# OSSIBeacon.net
KiCad netlist of a schematic drawn in EAGLE
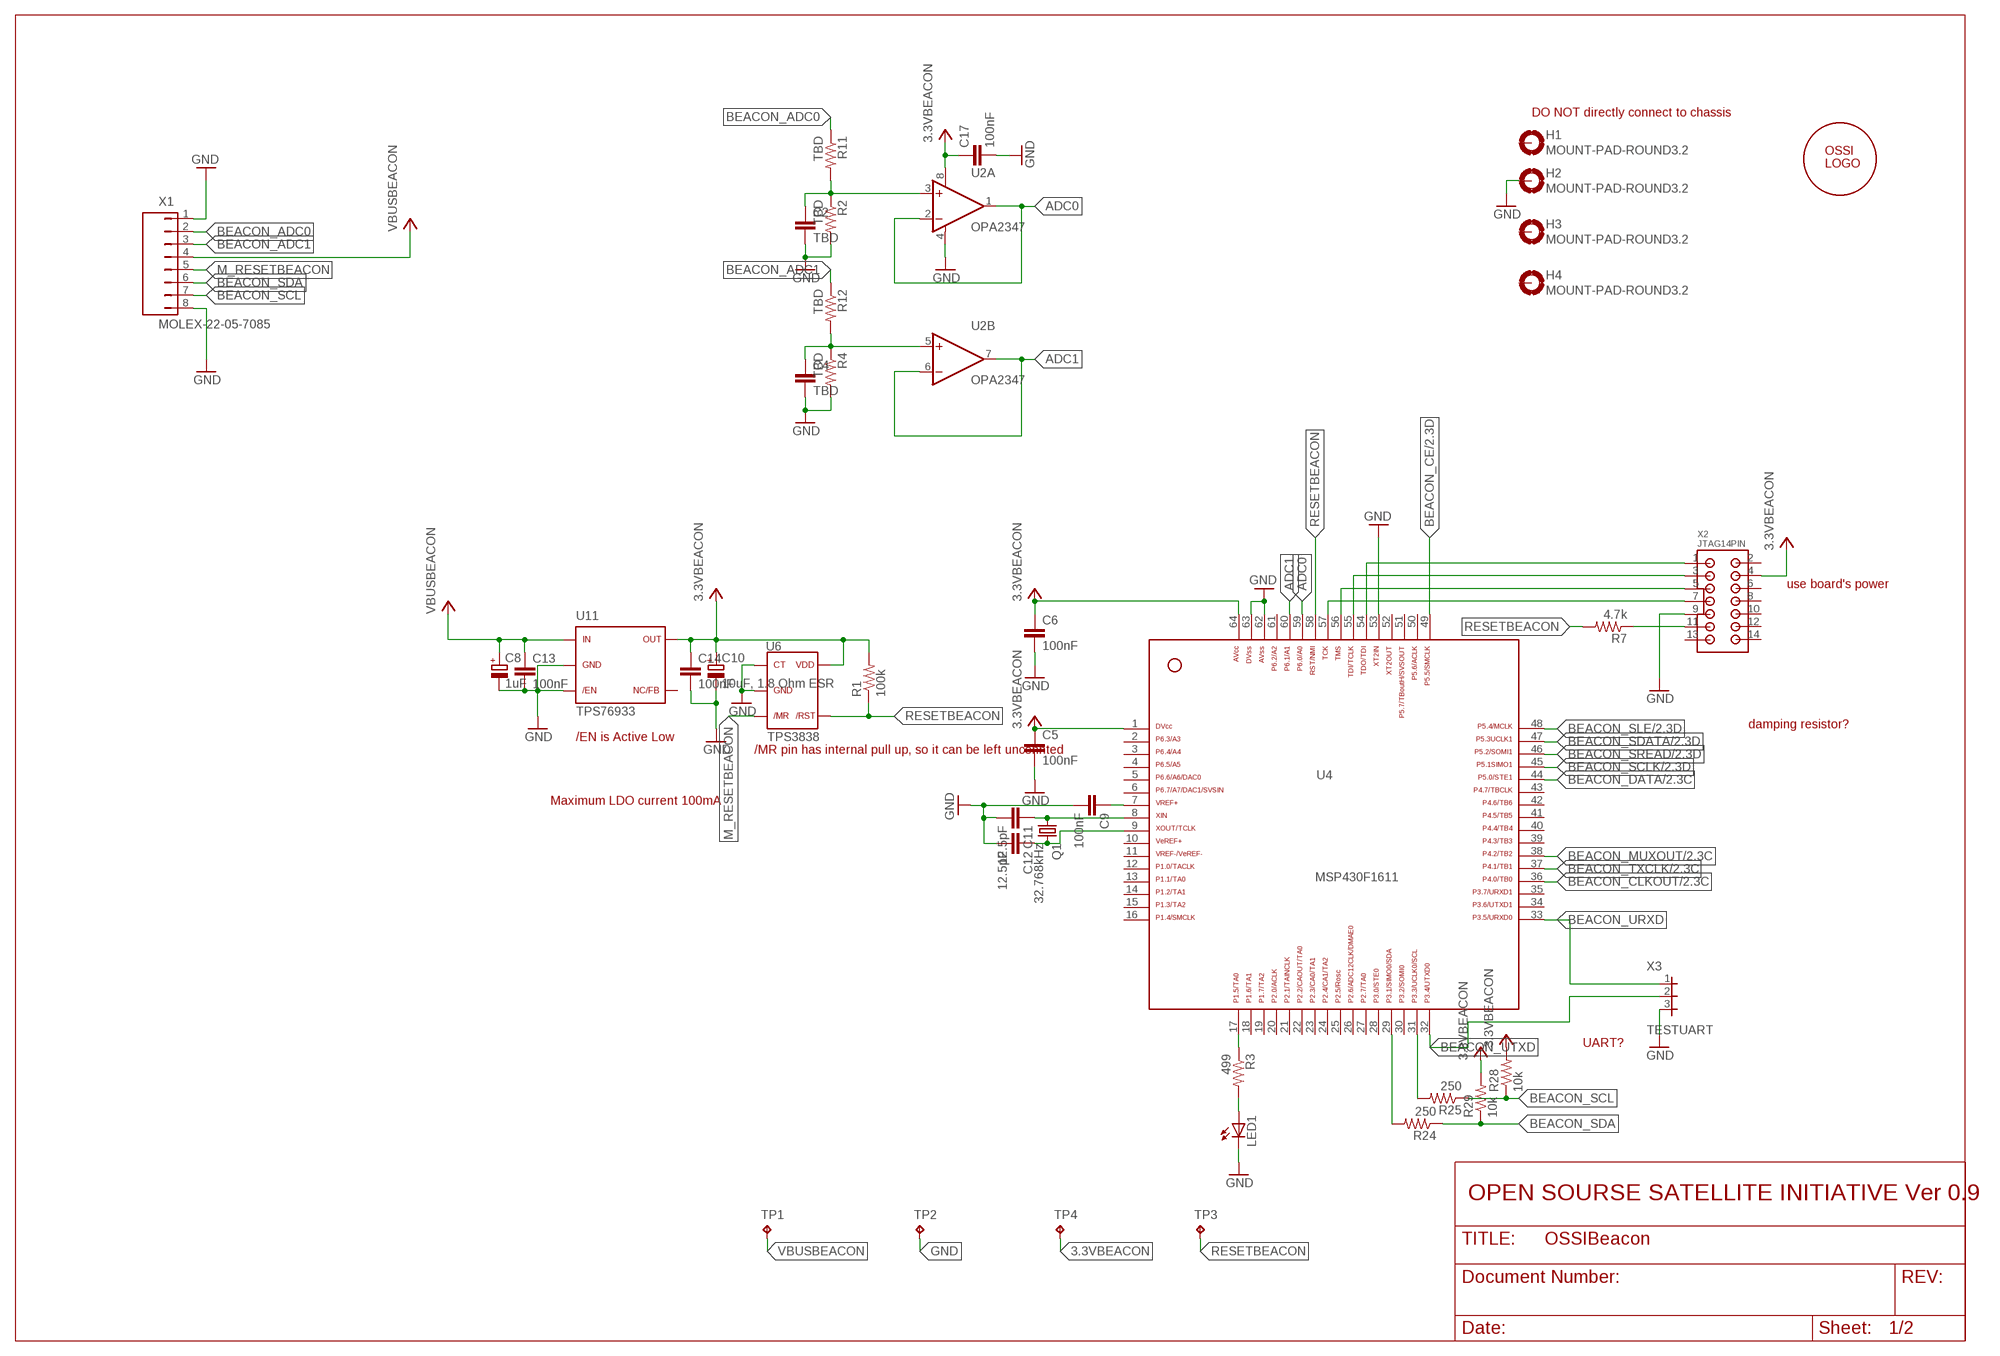
[diagram p0: schematic, sheet 1]
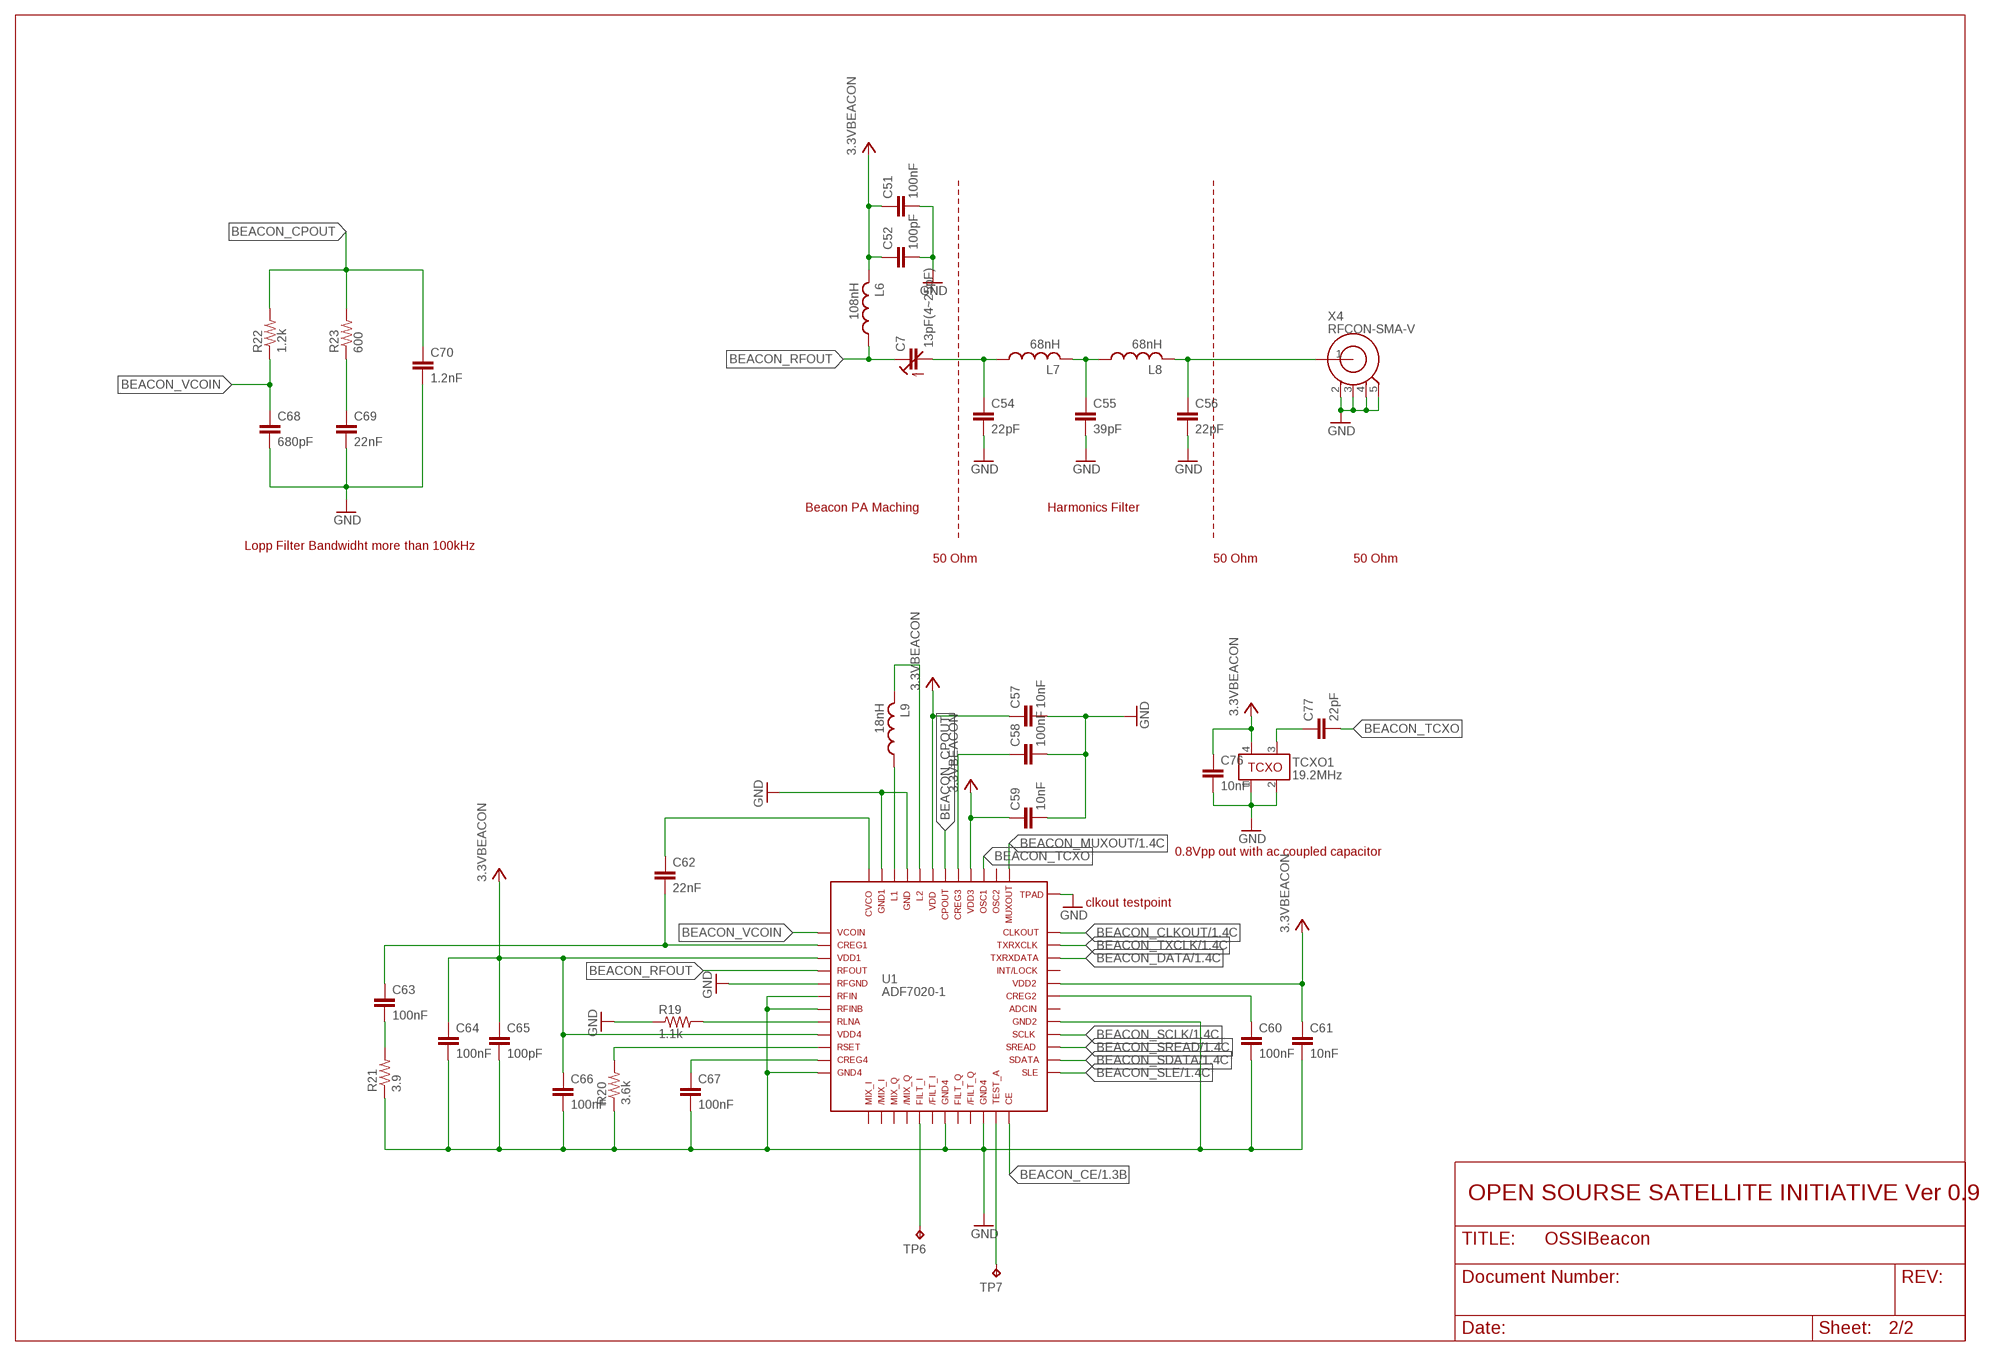
[diagram p1: schematic, sheet 2]

(export (version "E")
  (design (tool "Eeschema 10.0.6"))
  (components
    (comp (ref "C7")
      (value "13pF(4~25pF)")
      (footprint "eagle-import:TZB4Z250BA10R00")
      (libsource (lib "eagle-import") (part "C-TRIMM"))
    )
    (comp (ref "C51")
      (value "100nF")
      (footprint "eagle-import:C0603(1608)")
      (libsource (lib "eagle-import") (part "C0603(1608)"))
    )
    (comp (ref "C52")
      (value "100pF")
      (footprint "eagle-import:C0603(1608)")
      (libsource (lib "eagle-import") (part "C0603(1608)"))
    )
    (comp (ref "C54")
      (value "22pF")
      (footprint "eagle-import:C0603(1608)")
      (libsource (lib "eagle-import") (part "C0603(1608)"))
    )
    (comp (ref "C55")
      (value "39pF")
      (footprint "eagle-import:C0603(1608)")
      (libsource (lib "eagle-import") (part "C0603(1608)"))
    )
    (comp (ref "C56")
      (value "22pF")
      (footprint "eagle-import:C0603(1608)")
      (libsource (lib "eagle-import") (part "C0603(1608)"))
    )
    (comp (ref "C57")
      (value "10nF")
      (footprint "eagle-import:C0603(1608)")
      (libsource (lib "eagle-import") (part "C0603(1608)"))
    )
    (comp (ref "C58")
      (value "100nF")
      (footprint "eagle-import:C0603(1608)")
      (libsource (lib "eagle-import") (part "C0603(1608)"))
    )
    (comp (ref "C59")
      (value "10nF")
      (footprint "eagle-import:C0603(1608)")
      (libsource (lib "eagle-import") (part "C0603(1608)"))
    )
    (comp (ref "C60")
      (value "100nF")
      (footprint "eagle-import:C0603(1608)")
      (libsource (lib "eagle-import") (part "C0603(1608)"))
    )
    (comp (ref "C61")
      (value "10nF")
      (footprint "eagle-import:C0603(1608)")
      (libsource (lib "eagle-import") (part "C0603(1608)"))
    )
    (comp (ref "C62")
      (value "22nF")
      (footprint "eagle-import:C0603(1608)")
      (libsource (lib "eagle-import") (part "C0603(1608)"))
    )
    (comp (ref "C63")
      (value "100nF")
      (footprint "eagle-import:C0603(1608)")
      (libsource (lib "eagle-import") (part "C0603(1608)"))
    )
    (comp (ref "C64")
      (value "100nF")
      (footprint "eagle-import:C0603(1608)")
      (libsource (lib "eagle-import") (part "C0603(1608)"))
    )
    (comp (ref "C65")
      (value "100pF")
      (footprint "eagle-import:C0603(1608)")
      (libsource (lib "eagle-import") (part "C0603(1608)"))
    )
    (comp (ref "C66")
      (value "100nF")
      (footprint "eagle-import:C0603(1608)")
      (libsource (lib "eagle-import") (part "C0603(1608)"))
    )
    (comp (ref "C67")
      (value "100nF")
      (footprint "eagle-import:C0603(1608)")
      (libsource (lib "eagle-import") (part "C0603(1608)"))
    )
    (comp (ref "C68")
      (value "680pF")
      (footprint "eagle-import:C0603(1608)")
      (libsource (lib "eagle-import") (part "C0603(1608)"))
    )
    (comp (ref "C69")
      (value "22nF")
      (footprint "eagle-import:C0603(1608)")
      (libsource (lib "eagle-import") (part "C0603(1608)"))
    )
    (comp (ref "C70")
      (value "1.2nF")
      (footprint "eagle-import:C0603(1608)")
      (libsource (lib "eagle-import") (part "C0603(1608)"))
    )
    (comp (ref "C76")
      (value "10nF")
      (footprint "eagle-import:C0603(1608)")
      (libsource (lib "eagle-import") (part "C0603(1608)"))
    )
    (comp (ref "C77")
      (value "22pF")
      (footprint "eagle-import:C0603(1608)")
      (libsource (lib "eagle-import") (part "C0603(1608)"))
    )
    (comp (ref "L6")
      (value "108nH")
      (footprint "eagle-import:L0603(1608)")
      (libsource (lib "eagle-import") (part "L0603(1608)"))
    )
    (comp (ref "L7")
      (value "68nH")
      (footprint "eagle-import:L0603(1608)")
      (libsource (lib "eagle-import") (part "L0603(1608)"))
    )
    (comp (ref "L8")
      (value "68nH")
      (footprint "eagle-import:L0603(1608)")
      (libsource (lib "eagle-import") (part "L0603(1608)"))
    )
    (comp (ref "L9")
      (value "18nH")
      (footprint "eagle-import:L0603(1608)")
      (libsource (lib "eagle-import") (part "L0603(1608)"))
    )
    (comp (ref "R19")
      (value "1.1k")
      (footprint "eagle-import:R0603(1608)")
      (libsource (lib "eagle-import") (part "R0603(1608)"))
    )
    (comp (ref "R20")
      (value "3.6k")
      (footprint "eagle-import:R0603(1608)")
      (libsource (lib "eagle-import") (part "R0603(1608)"))
    )
    (comp (ref "R21")
      (value "3.9")
      (footprint "eagle-import:R0603(1608)")
      (libsource (lib "eagle-import") (part "R0603(1608)"))
    )
    (comp (ref "R22")
      (value "1.2k")
      (footprint "eagle-import:R0603(1608)")
      (libsource (lib "eagle-import") (part "R0603(1608)"))
    )
    (comp (ref "R23")
      (value "600")
      (footprint "eagle-import:R0603(1608)")
      (libsource (lib "eagle-import") (part "R0603(1608)"))
    )
    (comp (ref "TCXO1")
      (value "19.2MHz")
      (footprint "eagle-import:TCXO_M532")
      (libsource (lib "eagle-import") (part "TCXO-M532"))
    )
    (comp (ref "TP6")
      (value "TP")
      (footprint "eagle-import:TP-13")
      (libsource (lib "eagle-import") (part "TP"))
    )
    (comp (ref "TP7")
      (value "TP")
      (footprint "eagle-import:TP-13")
      (libsource (lib "eagle-import") (part "TP"))
    )
    (comp (ref "U1")
      (value "ADF7020-1")
      (footprint "eagle-import:LFCSP48")
      (libsource (lib "eagle-import") (part "ADF7020-1"))
    )
    (comp (ref "X4")
      (value "RFCON-SMA-V")
      (footprint "eagle-import:SMA-V")
      (libsource (lib "eagle-import") (part "RFCON-SMA-V"))
    )
    (comp (ref "C2")
      (value "TBD")
      (footprint "eagle-import:C0603(1608)")
      (libsource (lib "eagle-import") (part "C0603(1608)"))
    )
    (comp (ref "C4")
      (value "TBD")
      (footprint "eagle-import:C0603(1608)")
      (libsource (lib "eagle-import") (part "C0603(1608)"))
    )
    (comp (ref "C5")
      (value "100nF")
      (footprint "eagle-import:C0603(1608)")
      (libsource (lib "eagle-import") (part "C0603(1608)"))
    )
    (comp (ref "C6")
      (value "100nF")
      (footprint "eagle-import:C0603(1608)")
      (libsource (lib "eagle-import") (part "C0603(1608)"))
    )
    (comp (ref "C8")
      (value "1uF")
      (footprint "eagle-import:C1206(3216)-A")
      (libsource (lib "eagle-import") (part "C-TANTAL-A"))
    )
    (comp (ref "C9")
      (value "100nF")
      (footprint "eagle-import:C0603(1608)")
      (libsource (lib "eagle-import") (part "C0603(1608)"))
    )
    (comp (ref "C10")
      (value "10uF, 1.8 Ohm ESR")
      (footprint "eagle-import:C2312(6032)-C")
      (libsource (lib "eagle-import") (part "C-TANTAL-C"))
    )
    (comp (ref "C11")
      (value "12.5pF")
      (footprint "eagle-import:C0603(1608)")
      (libsource (lib "eagle-import") (part "C0603(1608)"))
    )
    (comp (ref "C12")
      (value "12.5pF")
      (footprint "eagle-import:C0603(1608)")
      (libsource (lib "eagle-import") (part "C0603(1608)"))
    )
    (comp (ref "C13")
      (value "100nF")
      (footprint "eagle-import:C0603(1608)")
      (libsource (lib "eagle-import") (part "C0603(1608)"))
    )
    (comp (ref "C14")
      (value "100nF")
      (footprint "eagle-import:C0603(1608)")
      (libsource (lib "eagle-import") (part "C0603(1608)"))
    )
    (comp (ref "C17")
      (value "100nF")
      (footprint "eagle-import:C0603(1608)")
      (libsource (lib "eagle-import") (part "C0603(1608)"))
    )
    (comp (ref "H1")
      (value "MOUNT-PAD-ROUND3.2")
      (footprint "eagle-import:3.2-PAD-ROUND")
      (libsource (lib "eagle-import") (part "MOUNT-PAD-ROUND3.2"))
    )
    (comp (ref "H2")
      (value "MOUNT-PAD-ROUND3.2")
      (footprint "eagle-import:3.2-PAD-ROUND")
      (libsource (lib "eagle-import") (part "MOUNT-PAD-ROUND3.2"))
    )
    (comp (ref "H3")
      (value "MOUNT-PAD-ROUND3.2")
      (footprint "eagle-import:3.2-PAD-ROUND")
      (libsource (lib "eagle-import") (part "MOUNT-PAD-ROUND3.2"))
    )
    (comp (ref "H4")
      (value "MOUNT-PAD-ROUND3.2")
      (footprint "eagle-import:3.2-PAD-ROUND")
      (libsource (lib "eagle-import") (part "MOUNT-PAD-ROUND3.2"))
    )
    (comp (ref "LED1")
      (value "LED3MM")
      (footprint "eagle-import:LED3MM")
      (libsource (lib "eagle-import") (part "LED3MM"))
    )
    (comp (ref "Q1")
      (value "32.768kHz")
      (footprint "eagle-import:NX-3215")
      (libsource (lib "eagle-import") (part "NX-3215"))
    )
    (comp (ref "R1")
      (value "100k")
      (footprint "eagle-import:R0603(1608)")
      (libsource (lib "eagle-import") (part "R0603(1608)"))
    )
    (comp (ref "R2")
      (value "TBD")
      (footprint "eagle-import:R0603(1608)")
      (libsource (lib "eagle-import") (part "R0603(1608)"))
    )
    (comp (ref "R3")
      (value "499")
      (footprint "eagle-import:R0603(1608)")
      (libsource (lib "eagle-import") (part "R0603(1608)"))
    )
    (comp (ref "R4")
      (value "TBD")
      (footprint "eagle-import:R0603(1608)")
      (libsource (lib "eagle-import") (part "R0603(1608)"))
    )
    (comp (ref "R7")
      (value "4.7k")
      (footprint "eagle-import:R0603(1608)")
      (libsource (lib "eagle-import") (part "R0603(1608)"))
    )
    (comp (ref "R11")
      (value "TBD")
      (footprint "eagle-import:R0603(1608)")
      (libsource (lib "eagle-import") (part "R0603(1608)"))
    )
    (comp (ref "R12")
      (value "TBD")
      (footprint "eagle-import:R0603(1608)")
      (libsource (lib "eagle-import") (part "R0603(1608)"))
    )
    (comp (ref "R24")
      (value "250")
      (footprint "eagle-import:R0603(1608)")
      (libsource (lib "eagle-import") (part "R0603(1608)"))
    )
    (comp (ref "R25")
      (value "250")
      (footprint "eagle-import:R0603(1608)")
      (libsource (lib "eagle-import") (part "R0603(1608)"))
    )
    (comp (ref "R28")
      (value "10k")
      (footprint "eagle-import:R0603(1608)")
      (libsource (lib "eagle-import") (part "R0603(1608)"))
    )
    (comp (ref "R29")
      (value "10k")
      (footprint "eagle-import:R0603(1608)")
      (libsource (lib "eagle-import") (part "R0603(1608)"))
    )
    (comp (ref "TP1")
      (value "TP")
      (footprint "eagle-import:TP-13")
      (libsource (lib "eagle-import") (part "TP"))
    )
    (comp (ref "TP2")
      (value "TP")
      (footprint "eagle-import:TP-13")
      (libsource (lib "eagle-import") (part "TP"))
    )
    (comp (ref "TP3")
      (value "TP")
      (footprint "eagle-import:TP-13")
      (libsource (lib "eagle-import") (part "TP"))
    )
    (comp (ref "TP4")
      (value "TP")
      (footprint "eagle-import:TP-13")
      (libsource (lib "eagle-import") (part "TP"))
    )
    (comp (ref "U$1")
      (value "OSSILOGO-10")
      (footprint "eagle-import:OSSILOGO1010")
      (libsource (lib "eagle-import") (part "OSSILOGO-10"))
    )
    (comp (ref "U2")
      (value "OPA2347")
      (footprint "eagle-import:SOT23-8DCN")
      (libsource (lib "eagle-import") (part "OPA2347"))
    )
    (comp (ref "U4")
      (value "MSP430F1611")
      (footprint "eagle-import:PM_PAG64")
      (libsource (lib "eagle-import") (part "MSP430F1611"))
    )
    (comp (ref "U6")
      (value "TPS3838")
      (footprint "eagle-import:SOT23-5DBV")
      (libsource (lib "eagle-import") (part "TPS3838"))
    )
    (comp (ref "U11")
      (value "TPS76933")
      (footprint "eagle-import:SOT23-5DBV")
      (libsource (lib "eagle-import") (part "TPS76933"))
    )
    (comp (ref "X1")
      (value "MOLEX-22-05-7085")
      (footprint "eagle-import:22-05-7085")
      (libsource (lib "eagle-import") (part "MOLEX-22-05-7085"))
    )
    (comp (ref "X2")
      (value "JTAG14PIN")
      (footprint "eagle-import:2514-6002UB")
      (libsource (lib "eagle-import") (part "JTAG14PIN"))
    )
    (comp (ref "X3")
      (value "TESTUART")
      (footprint "eagle-import:TESTUART")
      (libsource (lib "eagle-import") (part "TESTUART"))
    )
  )
  (nets
    (net (code "1") (name "3.3VBEACON") (class "Default")
      (node (ref "C10") (pin "1") (pinfunction "+_1") (pintype "passive"))
      (node (ref "C14") (pin "1") (pinfunction "1_1") (pintype "passive"))
      (node (ref "C17") (pin "1") (pinfunction "1_1") (pintype "passive"))
      (node (ref "C5") (pin "1") (pinfunction "1_1") (pintype "passive"))
      (node (ref "C51") (pin "1") (pinfunction "1_1") (pintype "passive"))
      (node (ref "C52") (pin "1") (pinfunction "1_1") (pintype "passive"))
      (node (ref "C57") (pin "1") (pinfunction "1_1") (pintype "passive"))
      (node (ref "C59") (pin "1") (pinfunction "1_1") (pintype "passive"))
      (node (ref "C6") (pin "1") (pinfunction "1_1") (pintype "passive"))
      (node (ref "C61") (pin "1") (pinfunction "1_1") (pintype "passive"))
      (node (ref "C64") (pin "1") (pinfunction "1_1") (pintype "passive"))
      (node (ref "C65") (pin "1") (pinfunction "1_1") (pintype "passive"))
      (node (ref "C66") (pin "1") (pinfunction "1_1") (pintype "passive"))
      (node (ref "C76") (pin "1") (pinfunction "1_1") (pintype "passive"))
      (node (ref "L6") (pin "2") (pinfunction "2_2") (pintype "passive"))
      (node (ref "R1") (pin "2") (pinfunction "2_2") (pintype "passive"))
      (node (ref "R28") (pin "2") (pinfunction "2_2") (pintype "passive"))
      (node (ref "R29") (pin "2") (pinfunction "2_2") (pintype "passive"))
      (node (ref "TCXO1") (pin "4") (pinfunction "P$4_4") (pintype "bidirectional"))
      (node (ref "TP4") (pin "TP") (pinfunction "TP_TP") (pintype "input"))
      (node (ref "U1") (pin "3") (pinfunction "P$3_3") (pintype "bidirectional"))
      (node (ref "U1") (pin "32") (pinfunction "P$32_32") (pintype "bidirectional"))
      (node (ref "U1") (pin "40") (pinfunction "P$40_40") (pintype "bidirectional"))
      (node (ref "U1") (pin "43") (pinfunction "P$43_43") (pintype "bidirectional"))
      (node (ref "U1") (pin "9") (pinfunction "P$9_9") (pintype "bidirectional"))
      (node (ref "U11") (pin "5") (pinfunction "5_5") (pintype "power_in"))
      (node (ref "U2") (pin "8") (pinfunction "V+_8") (pintype "power_in"))
      (node (ref "U4") (pin "1") (pinfunction "1_1") (pintype "power_in"))
      (node (ref "U4") (pin "64") (pinfunction "64_64") (pintype "power_in"))
      (node (ref "U6") (pin "5") (pinfunction "P$5_5") (pintype "power_in"))
      (node (ref "X2") (pin "4") (pinfunction "4_4") (pintype "bidirectional"))
    )
    (net (code "2") (name "ADC0") (class "Default")
      (node (ref "U2") (pin "1") (pinfunction "OUT_1") (pintype "output"))
      (node (ref "U2") (pin "2") (pinfunction "-IN_2") (pintype "input"))
      (node (ref "U4") (pin "59") (pinfunction "59_59") (pintype "bidirectional"))
    )
    (net (code "3") (name "ADC1") (class "Default")
      (node (ref "U2") (pin "6") (pinfunction "-IN_6") (pintype "input"))
      (node (ref "U2") (pin "7") (pinfunction "OUT_7") (pintype "output"))
      (node (ref "U4") (pin "60") (pinfunction "60_60") (pintype "bidirectional"))
    )
    (net (code "4") (name "BEACON_ADC0") (class "Default")
      (node (ref "R11") (pin "1") (pinfunction "1_1") (pintype "passive"))
      (node (ref "X1") (pin "2") (pinfunction "2_2") (pintype "passive"))
    )
    (net (code "5") (name "BEACON_ADC1") (class "Default")
      (node (ref "R12") (pin "1") (pinfunction "1_1") (pintype "passive"))
      (node (ref "X1") (pin "3") (pinfunction "3_3") (pintype "passive"))
    )
    (net (code "6") (name "BEACON_CE") (class "Default")
      (node (ref "U1") (pin "24") (pinfunction "P$24_24") (pintype "bidirectional"))
      (node (ref "U4") (pin "49") (pinfunction "49_49") (pintype "bidirectional"))
    )
    (net (code "7") (name "BEACON_CLKOUT") (class "Default")
      (node (ref "U1") (pin "36") (pinfunction "P$36_36") (pintype "bidirectional"))
      (node (ref "U4") (pin "36") (pinfunction "36_36") (pintype "output"))
    )
    (net (code "8") (name "BEACON_CPOUT") (class "Default")
      (node (ref "C70") (pin "1") (pinfunction "1_1") (pintype "passive"))
      (node (ref "R22") (pin "2") (pinfunction "2_2") (pintype "passive"))
      (node (ref "R23") (pin "2") (pinfunction "2_2") (pintype "passive"))
      (node (ref "U1") (pin "42") (pinfunction "P$42_42") (pintype "bidirectional"))
    )
    (net (code "9") (name "BEACON_DATA") (class "Default")
      (node (ref "U1") (pin "34") (pinfunction "P$34_34") (pintype "bidirectional"))
      (node (ref "U4") (pin "44") (pinfunction "44_44") (pintype "bidirectional"))
    )
    (net (code "10") (name "BEACON_MUXOUT") (class "Default")
      (node (ref "U1") (pin "37") (pinfunction "P$37_37") (pintype "bidirectional"))
      (node (ref "U4") (pin "38") (pinfunction "38_38") (pintype "bidirectional"))
    )
    (net (code "11") (name "BEACON_RFOUT") (class "Default")
      (node (ref "C7") (pin "+") (pinfunction "E_+") (pintype "passive"))
      (node (ref "L6") (pin "1") (pinfunction "1_1") (pintype "passive"))
      (node (ref "U1") (pin "4") (pinfunction "P$4_4") (pintype "bidirectional"))
    )
    (net (code "12") (name "BEACON_SCL") (class "Default")
      (node (ref "R25") (pin "1") (pinfunction "1_1") (pintype "passive"))
      (node (ref "R28") (pin "1") (pinfunction "1_1") (pintype "passive"))
      (node (ref "X1") (pin "7") (pinfunction "7_7") (pintype "passive"))
    )
    (net (code "13") (name "BEACON_SCLK") (class "Default")
      (node (ref "U1") (pin "28") (pinfunction "P$28_28") (pintype "bidirectional"))
      (node (ref "U4") (pin "45") (pinfunction "45_45") (pintype "bidirectional"))
    )
    (net (code "14") (name "BEACON_SDA") (class "Default")
      (node (ref "R24") (pin "1") (pinfunction "1_1") (pintype "passive"))
      (node (ref "R29") (pin "1") (pinfunction "1_1") (pintype "passive"))
      (node (ref "X1") (pin "6") (pinfunction "6_6") (pintype "passive"))
    )
    (net (code "15") (name "BEACON_SDATA") (class "Default")
      (node (ref "U1") (pin "26") (pinfunction "P$26_26") (pintype "bidirectional"))
      (node (ref "U4") (pin "47") (pinfunction "47_47") (pintype "bidirectional"))
    )
    (net (code "16") (name "BEACON_SLE") (class "Default")
      (node (ref "U1") (pin "25") (pinfunction "P$25_25") (pintype "bidirectional"))
      (node (ref "U4") (pin "48") (pinfunction "48_48") (pintype "bidirectional"))
    )
    (net (code "17") (name "BEACON_SREAD") (class "Default")
      (node (ref "U1") (pin "27") (pinfunction "P$27_27") (pintype "bidirectional"))
      (node (ref "U4") (pin "46") (pinfunction "46_46") (pintype "bidirectional"))
    )
    (net (code "18") (name "BEACON_TCXO") (class "Default")
      (node (ref "C77") (pin "2") (pinfunction "2_2") (pintype "passive"))
      (node (ref "U1") (pin "39") (pinfunction "P$39_39") (pintype "bidirectional"))
    )
    (net (code "19") (name "BEACON_TXCLK") (class "Default")
      (node (ref "U1") (pin "35") (pinfunction "P$35_35") (pintype "bidirectional"))
      (node (ref "U4") (pin "37") (pinfunction "37_37") (pintype "bidirectional"))
    )
    (net (code "20") (name "BEACON_URXD") (class "Default")
      (node (ref "U4") (pin "33") (pinfunction "33_33") (pintype "bidirectional"))
      (node (ref "X3") (pin "1") (pinfunction "1_1") (pintype "bidirectional"))
    )
    (net (code "21") (name "BEACON_UTXD") (class "Default")
      (node (ref "U4") (pin "32") (pinfunction "32_32") (pintype "bidirectional"))
      (node (ref "X3") (pin "2") (pinfunction "2_2") (pintype "bidirectional"))
    )
    (net (code "22") (name "BEACON_VCOIN") (class "Default")
      (node (ref "C68") (pin "1") (pinfunction "1_1") (pintype "passive"))
      (node (ref "R22") (pin "1") (pinfunction "1_1") (pintype "passive"))
      (node (ref "U1") (pin "1") (pinfunction "P$1_1") (pintype "bidirectional"))
    )
    (net (code "23") (name "GND") (class "Default")
      (node (ref "C10") (pin "2") (pinfunction "-_2") (pintype "passive"))
      (node (ref "C11") (pin "2") (pinfunction "2_2") (pintype "passive"))
      (node (ref "C12") (pin "2") (pinfunction "2_2") (pintype "passive"))
      (node (ref "C13") (pin "2") (pinfunction "2_2") (pintype "passive"))
      (node (ref "C14") (pin "2") (pinfunction "2_2") (pintype "passive"))
      (node (ref "C17") (pin "2") (pinfunction "2_2") (pintype "passive"))
      (node (ref "C2") (pin "2") (pinfunction "2_2") (pintype "passive"))
      (node (ref "C4") (pin "2") (pinfunction "2_2") (pintype "passive"))
      (node (ref "C5") (pin "2") (pinfunction "2_2") (pintype "passive"))
      (node (ref "C51") (pin "2") (pinfunction "2_2") (pintype "passive"))
      (node (ref "C52") (pin "2") (pinfunction "2_2") (pintype "passive"))
      (node (ref "C54") (pin "2") (pinfunction "2_2") (pintype "passive"))
      (node (ref "C55") (pin "2") (pinfunction "2_2") (pintype "passive"))
      (node (ref "C56") (pin "2") (pinfunction "2_2") (pintype "passive"))
      (node (ref "C57") (pin "2") (pinfunction "2_2") (pintype "passive"))
      (node (ref "C58") (pin "2") (pinfunction "2_2") (pintype "passive"))
      (node (ref "C59") (pin "2") (pinfunction "2_2") (pintype "passive"))
      (node (ref "C6") (pin "2") (pinfunction "2_2") (pintype "passive"))
      (node (ref "C60") (pin "2") (pinfunction "2_2") (pintype "passive"))
      (node (ref "C61") (pin "2") (pinfunction "2_2") (pintype "passive"))
      (node (ref "C64") (pin "2") (pinfunction "2_2") (pintype "passive"))
      (node (ref "C65") (pin "2") (pinfunction "2_2") (pintype "passive"))
      (node (ref "C66") (pin "2") (pinfunction "2_2") (pintype "passive"))
      (node (ref "C67") (pin "2") (pinfunction "2_2") (pintype "passive"))
      (node (ref "C68") (pin "2") (pinfunction "2_2") (pintype "passive"))
      (node (ref "C69") (pin "2") (pinfunction "2_2") (pintype "passive"))
      (node (ref "C70") (pin "2") (pinfunction "2_2") (pintype "passive"))
      (node (ref "C76") (pin "2") (pinfunction "2_2") (pintype "passive"))
      (node (ref "C8") (pin "2") (pinfunction "-_2") (pintype "passive"))
      (node (ref "C9") (pin "2") (pinfunction "2_2") (pintype "passive"))
      (node (ref "H2") (pin "B3,2") (pinfunction "MOUNT_B3,2") (pintype "passive"))
      (node (ref "LED1") (pin "K") (pinfunction "C_K") (pintype "passive"))
      (node (ref "R19") (pin "1") (pinfunction "1_1") (pintype "passive"))
      (node (ref "R2") (pin "2") (pinfunction "2_2") (pintype "passive"))
      (node (ref "R20") (pin "1") (pinfunction "1_1") (pintype "passive"))
      (node (ref "R21") (pin "1") (pinfunction "1_1") (pintype "passive"))
      (node (ref "R4") (pin "2") (pinfunction "2_2") (pintype "passive"))
      (node (ref "TCXO1") (pin "1") (pinfunction "P$1_1") (pintype "bidirectional"))
      (node (ref "TCXO1") (pin "2") (pinfunction "P$2_2") (pintype "bidirectional"))
      (node (ref "TP2") (pin "TP") (pinfunction "TP_TP") (pintype "input"))
      (node (ref "U1") (pin "12") (pinfunction "P$12_12") (pintype "bidirectional"))
      (node (ref "U1") (pin "19") (pinfunction "P$19_19") (pintype "bidirectional"))
      (node (ref "U1") (pin "22") (pinfunction "P$22_22") (pintype "bidirectional"))
      (node (ref "U1") (pin "29") (pinfunction "P$29_29") (pintype "bidirectional"))
      (node (ref "U1") (pin "45") (pinfunction "P$45_45") (pintype "bidirectional"))
      (node (ref "U1") (pin "47") (pinfunction "P$47_47") (pintype "bidirectional"))
      (node (ref "U1") (pin "5") (pinfunction "P$5_5") (pintype "bidirectional"))
      (node (ref "U1") (pin "6") (pinfunction "P$6_6") (pintype "bidirectional"))
      (node (ref "U1") (pin "7") (pinfunction "P$7_7") (pintype "bidirectional"))
      (node (ref "U1") (pin "EXP") (pinfunction "P$49_EXP") (pintype "bidirectional"))
      (node (ref "U11") (pin "2") (pinfunction "2_2") (pintype "power_in"))
      (node (ref "U11") (pin "3") (pinfunction "3_3") (pintype "input"))
      (node (ref "U2") (pin "4") (pinfunction "V-_4") (pintype "power_in"))
      (node (ref "U4") (pin "53") (pinfunction "53_53") (pintype "input"))
      (node (ref "U4") (pin "62") (pinfunction "62_62") (pintype "power_in"))
      (node (ref "U4") (pin "63") (pinfunction "63_63") (pintype "power_in"))
      (node (ref "U6") (pin "1") (pinfunction "P$1_1") (pintype "bidirectional"))
      (node (ref "U6") (pin "2") (pinfunction "P$2_2") (pintype "power_in"))
      (node (ref "X1") (pin "1") (pinfunction "1_1") (pintype "passive"))
      (node (ref "X1") (pin "8") (pinfunction "8_8") (pintype "passive"))
      (node (ref "X2") (pin "9") (pinfunction "9_9") (pintype "bidirectional"))
      (node (ref "X3") (pin "3") (pinfunction "3_3") (pintype "bidirectional"))
      (node (ref "X4") (pin "2") (pinfunction "2_2") (pintype "power_in"))
      (node (ref "X4") (pin "3") (pinfunction "3_3") (pintype "power_in"))
      (node (ref "X4") (pin "4") (pinfunction "4_4") (pintype "power_in"))
      (node (ref "X4") (pin "5") (pinfunction "5_5") (pintype "power_in"))
    )
    (net (code "24") (name "M_RESETBEACON") (class "Default")
      (node (ref "U6") (pin "3") (pinfunction "P$3_3") (pintype "input"))
      (node (ref "X1") (pin "5") (pinfunction "5_5") (pintype "passive"))
    )
    (net (code "25") (name "Net-(C7-A)") (class "Default")
      (node (ref "C54") (pin "1") (pinfunction "1_1") (pintype "passive"))
      (node (ref "C7") (pin "-") (pinfunction "A_-") (pintype "passive"))
      (node (ref "L7") (pin "1") (pinfunction "1_1") (pintype "passive"))
    )
    (net (code "26") (name "Net-(C9-Pad1)") (class "Default")
      (node (ref "C9") (pin "1") (pinfunction "1_1") (pintype "passive"))
      (node (ref "U4") (pin "7") (pinfunction "7_7") (pintype "output"))
    )
    (net (code "27") (name "Net-(C11-Pad1)") (class "Default")
      (node (ref "C11") (pin "1") (pinfunction "1_1") (pintype "passive"))
      (node (ref "Q1") (pin "1") (pinfunction "1_1") (pintype "passive"))
      (node (ref "U4") (pin "8") (pinfunction "8_8") (pintype "input"))
    )
    (net (code "28") (name "Net-(C12-Pad1)") (class "Default")
      (node (ref "C12") (pin "1") (pinfunction "1_1") (pintype "passive"))
      (node (ref "Q1") (pin "2") (pinfunction "2_2") (pintype "passive"))
      (node (ref "U4") (pin "9") (pinfunction "9_9") (pintype "bidirectional"))
    )
    (net (code "29") (name "Net-(C55-Pad1)") (class "Default")
      (node (ref "C55") (pin "1") (pinfunction "1_1") (pintype "passive"))
      (node (ref "L7") (pin "2") (pinfunction "2_2") (pintype "passive"))
      (node (ref "L8") (pin "1") (pinfunction "1_1") (pintype "passive"))
    )
    (net (code "30") (name "Net-(C56-Pad1)") (class "Default")
      (node (ref "C56") (pin "1") (pinfunction "1_1") (pintype "passive"))
      (node (ref "L8") (pin "2") (pinfunction "2_2") (pintype "passive"))
      (node (ref "X4") (pin "1") (pinfunction "1_1") (pintype "bidirectional"))
    )
    (net (code "31") (name "Net-(C63-Pad2)") (class "Default")
      (node (ref "C63") (pin "2") (pinfunction "2_2") (pintype "passive"))
      (node (ref "R21") (pin "2") (pinfunction "2_2") (pintype "passive"))
    )
    (net (code "32") (name "Net-(C69-Pad1)") (class "Default")
      (node (ref "C69") (pin "1") (pinfunction "1_1") (pintype "passive"))
      (node (ref "R23") (pin "1") (pinfunction "1_1") (pintype "passive"))
    )
    (net (code "33") (name "Net-(LED1-PadA)") (class "Default")
      (node (ref "LED1") (pin "A") (pinfunction "A_A") (pintype "passive"))
      (node (ref "R3") (pin "2") (pinfunction "2_2") (pintype "passive"))
    )
    (net (code "34") (name "Net-(R3-Pad1)") (class "Default")
      (node (ref "R3") (pin "1") (pinfunction "1_1") (pintype "passive"))
      (node (ref "U4") (pin "17") (pinfunction "17_17") (pintype "bidirectional"))
    )
    (net (code "35") (name "Net-(R7-Pad1)") (class "Default")
      (node (ref "R7") (pin "1") (pinfunction "1_1") (pintype "passive"))
      (node (ref "X2") (pin "11") (pinfunction "11_11") (pintype "bidirectional"))
    )
    (net (code "36") (name "Net-(R24-Pad2)") (class "Default")
      (node (ref "R24") (pin "2") (pinfunction "2_2") (pintype "passive"))
      (node (ref "U4") (pin "29") (pinfunction "29_29") (pintype "bidirectional"))
    )
    (net (code "37") (name "Net-(R25-Pad2)") (class "Default")
      (node (ref "R25") (pin "2") (pinfunction "2_2") (pintype "passive"))
      (node (ref "U4") (pin "31") (pinfunction "31_31") (pintype "bidirectional"))
    )
    (net (code "38") (name "Net-(TCXO1-P$3)") (class "Default")
      (node (ref "C77") (pin "1") (pinfunction "1_1") (pintype "passive"))
      (node (ref "TCXO1") (pin "3") (pinfunction "P$3_3") (pintype "bidirectional"))
    )
    (net (code "39") (name "Net-(U1-P$2)") (class "Default")
      (node (ref "C62") (pin "2") (pinfunction "2_2") (pintype "passive"))
      (node (ref "C63") (pin "1") (pinfunction "1_1") (pintype "passive"))
      (node (ref "U1") (pin "2") (pinfunction "P$2_2") (pintype "bidirectional"))
    )
    (net (code "40") (name "Net-(U1-P$8)") (class "Default")
      (node (ref "R19") (pin "2") (pinfunction "2_2") (pintype "passive"))
      (node (ref "U1") (pin "8") (pinfunction "P$8_8") (pintype "bidirectional"))
    )
    (net (code "41") (name "Net-(U1-P$10)") (class "Default")
      (node (ref "R20") (pin "2") (pinfunction "2_2") (pintype "passive"))
      (node (ref "U1") (pin "10") (pinfunction "P$10_10") (pintype "bidirectional"))
    )
    (net (code "42") (name "Net-(U1-P$11)") (class "Default")
      (node (ref "C67") (pin "1") (pinfunction "1_1") (pintype "passive"))
      (node (ref "U1") (pin "11") (pinfunction "P$11_11") (pintype "bidirectional"))
    )
    (net (code "43") (name "Net-(U1-P$17)") (class "Default")
      (node (ref "TP6") (pin "TP") (pinfunction "TP_TP") (pintype "input"))
      (node (ref "U1") (pin "17") (pinfunction "P$17_17") (pintype "bidirectional"))
    )
    (net (code "44") (name "Net-(U1-P$23)") (class "Default")
      (node (ref "TP7") (pin "TP") (pinfunction "TP_TP") (pintype "input"))
      (node (ref "U1") (pin "23") (pinfunction "P$23_23") (pintype "bidirectional"))
    )
    (net (code "45") (name "Net-(U1-P$31)") (class "Default")
      (node (ref "C60") (pin "1") (pinfunction "1_1") (pintype "passive"))
      (node (ref "U1") (pin "31") (pinfunction "P$31_31") (pintype "bidirectional"))
    )
    (net (code "46") (name "Net-(U1-P$41)") (class "Default")
      (node (ref "C58") (pin "1") (pinfunction "1_1") (pintype "passive"))
      (node (ref "U1") (pin "41") (pinfunction "P$41_41") (pintype "bidirectional"))
    )
    (net (code "47") (name "Net-(U1-P$44)") (class "Default")
      (node (ref "L9") (pin "2") (pinfunction "2_2") (pintype "passive"))
      (node (ref "U1") (pin "44") (pinfunction "P$44_44") (pintype "bidirectional"))
    )
    (net (code "48") (name "Net-(U1-P$46)") (class "Default")
      (node (ref "L9") (pin "1") (pinfunction "1_1") (pintype "passive"))
      (node (ref "U1") (pin "46") (pinfunction "P$46_46") (pintype "bidirectional"))
    )
    (net (code "49") (name "Net-(U1-P$48)") (class "Default")
      (node (ref "C62") (pin "1") (pinfunction "1_1") (pintype "passive"))
      (node (ref "U1") (pin "48") (pinfunction "P$48_48") (pintype "bidirectional"))
    )
    (net (code "50") (name "Net-(U2A-+IN)") (class "Default")
      (node (ref "C2") (pin "1") (pinfunction "1_1") (pintype "passive"))
      (node (ref "R11") (pin "2") (pinfunction "2_2") (pintype "passive"))
      (node (ref "R2") (pin "1") (pinfunction "1_1") (pintype "passive"))
      (node (ref "U2") (pin "3") (pinfunction "+IN_3") (pintype "input"))
    )
    (net (code "51") (name "Net-(U2B-+IN)") (class "Default")
      (node (ref "C4") (pin "1") (pinfunction "1_1") (pintype "passive"))
      (node (ref "R12") (pin "2") (pinfunction "2_2") (pintype "passive"))
      (node (ref "R4") (pin "1") (pinfunction "1_1") (pintype "passive"))
      (node (ref "U2") (pin "5") (pinfunction "+IN_5") (pintype "input"))
    )
    (net (code "52") (name "Net-(U4-Pad54)") (class "Default")
      (node (ref "U4") (pin "54") (pinfunction "54_54") (pintype "bidirectional"))
      (node (ref "X2") (pin "1") (pinfunction "1_1") (pintype "bidirectional"))
    )
    (net (code "53") (name "Net-(U4-Pad55)") (class "Default")
      (node (ref "U4") (pin "55") (pinfunction "55_55") (pintype "input"))
      (node (ref "X2") (pin "3") (pinfunction "3_3") (pintype "bidirectional"))
    )
    (net (code "54") (name "Net-(U4-Pad56)") (class "Default")
      (node (ref "U4") (pin "56") (pinfunction "56_56") (pintype "input"))
      (node (ref "X2") (pin "5") (pinfunction "5_5") (pintype "bidirectional"))
    )
    (net (code "55") (name "Net-(U4-Pad57)") (class "Default")
      (node (ref "U4") (pin "57") (pinfunction "57_57") (pintype "input"))
      (node (ref "X2") (pin "7") (pinfunction "7_7") (pintype "bidirectional"))
    )
    (net (code "56") (name "RESETBEACON") (class "Default")
      (node (ref "R1") (pin "1") (pinfunction "1_1") (pintype "passive"))
      (node (ref "R7") (pin "2") (pinfunction "2_2") (pintype "passive"))
      (node (ref "TP3") (pin "TP") (pinfunction "TP_TP") (pintype "input"))
      (node (ref "U4") (pin "58") (pinfunction "58_58") (pintype "input"))
      (node (ref "U6") (pin "4") (pinfunction "P$4_4") (pintype "output"))
    )
    (net (code "57") (name "VBUSBEACON") (class "Default")
      (node (ref "C13") (pin "1") (pinfunction "1_1") (pintype "passive"))
      (node (ref "C8") (pin "1") (pinfunction "+_1") (pintype "passive"))
      (node (ref "TP1") (pin "TP") (pinfunction "TP_TP") (pintype "input"))
      (node (ref "U11") (pin "1") (pinfunction "1_1") (pintype "power_in"))
      (node (ref "X1") (pin "4") (pinfunction "4_4") (pintype "passive"))
    )
    (net (code "58") (name "unconnected-(H1-MOUNT-PadB3,2)") (class "Default")
      (node (ref "H1") (pin "B3,2") (pinfunction "MOUNT_B3,2") (pintype "passive"))
    )
    (net (code "59") (name "unconnected-(H3-MOUNT-PadB3,2)") (class "Default")
      (node (ref "H3") (pin "B3,2") (pinfunction "MOUNT_B3,2") (pintype "passive"))
    )
    (net (code "60") (name "unconnected-(H4-MOUNT-PadB3,2)") (class "Default")
      (node (ref "H4") (pin "B3,2") (pinfunction "MOUNT_B3,2") (pintype "passive"))
    )
    (net (code "61") (name "unconnected-(U1-P$13-Pad13)") (class "Default")
      (node (ref "U1") (pin "13") (pinfunction "P$13_13") (pintype "bidirectional"))
    )
    (net (code "62") (name "unconnected-(U1-P$14-Pad14)") (class "Default")
      (node (ref "U1") (pin "14") (pinfunction "P$14_14") (pintype "bidirectional"))
    )
    (net (code "63") (name "unconnected-(U1-P$15-Pad15)") (class "Default")
      (node (ref "U1") (pin "15") (pinfunction "P$15_15") (pintype "bidirectional"))
    )
    (net (code "64") (name "unconnected-(U1-P$16-Pad16)") (class "Default")
      (node (ref "U1") (pin "16") (pinfunction "P$16_16") (pintype "bidirectional"))
    )
    (net (code "65") (name "unconnected-(U1-P$18-Pad18)") (class "Default")
      (node (ref "U1") (pin "18") (pinfunction "P$18_18") (pintype "bidirectional"))
    )
    (net (code "66") (name "unconnected-(U1-P$20-Pad20)") (class "Default")
      (node (ref "U1") (pin "20") (pinfunction "P$20_20") (pintype "bidirectional"))
    )
    (net (code "67") (name "unconnected-(U1-P$21-Pad21)") (class "Default")
      (node (ref "U1") (pin "21") (pinfunction "P$21_21") (pintype "bidirectional"))
    )
    (net (code "68") (name "unconnected-(U1-P$30-Pad30)") (class "Default")
      (node (ref "U1") (pin "30") (pinfunction "P$30_30") (pintype "bidirectional"))
    )
    (net (code "69") (name "unconnected-(U1-P$33-Pad33)") (class "Default")
      (node (ref "U1") (pin "33") (pinfunction "P$33_33") (pintype "bidirectional"))
    )
    (net (code "70") (name "unconnected-(U1-P$38-Pad38)") (class "Default")
      (node (ref "U1") (pin "38") (pinfunction "P$38_38") (pintype "bidirectional"))
    )
    (net (code "71") (name "unconnected-(U4-Pad2)") (class "Default")
      (node (ref "U4") (pin "2") (pinfunction "2_2") (pintype "bidirectional"))
    )
    (net (code "72") (name "unconnected-(U4-Pad3)") (class "Default")
      (node (ref "U4") (pin "3") (pinfunction "3_3") (pintype "bidirectional"))
    )
    (net (code "73") (name "unconnected-(U4-Pad4)") (class "Default")
      (node (ref "U4") (pin "4") (pinfunction "4_4") (pintype "bidirectional"))
    )
    (net (code "74") (name "unconnected-(U4-Pad5)") (class "Default")
      (node (ref "U4") (pin "5") (pinfunction "5_5") (pintype "bidirectional"))
    )
    (net (code "75") (name "unconnected-(U4-Pad6)") (class "Default")
      (node (ref "U4") (pin "6") (pinfunction "6_6") (pintype "bidirectional"))
    )
    (net (code "76") (name "unconnected-(U4-Pad10)") (class "Default")
      (node (ref "U4") (pin "10") (pinfunction "10_10") (pintype "input"))
    )
    (net (code "77") (name "unconnected-(U4-Pad11)") (class "Default")
      (node (ref "U4") (pin "11") (pinfunction "11_11") (pintype "bidirectional"))
    )
    (net (code "78") (name "unconnected-(U4-Pad12)") (class "Default")
      (node (ref "U4") (pin "12") (pinfunction "12_12") (pintype "bidirectional"))
    )
    (net (code "79") (name "unconnected-(U4-Pad13)") (class "Default")
      (node (ref "U4") (pin "13") (pinfunction "13_13") (pintype "bidirectional"))
    )
    (net (code "80") (name "unconnected-(U4-Pad14)") (class "Default")
      (node (ref "U4") (pin "14") (pinfunction "14_14") (pintype "bidirectional"))
    )
    (net (code "81") (name "unconnected-(U4-Pad15)") (class "Default")
      (node (ref "U4") (pin "15") (pinfunction "15_15") (pintype "bidirectional"))
    )
    (net (code "82") (name "unconnected-(U4-Pad16)") (class "Default")
      (node (ref "U4") (pin "16") (pinfunction "16_16") (pintype "bidirectional"))
    )
    (net (code "83") (name "unconnected-(U4-Pad18)") (class "Default")
      (node (ref "U4") (pin "18") (pinfunction "18_18") (pintype "bidirectional"))
    )
    (net (code "84") (name "unconnected-(U4-Pad19)") (class "Default")
      (node (ref "U4") (pin "19") (pinfunction "19_19") (pintype "bidirectional"))
    )
    (net (code "85") (name "unconnected-(U4-Pad20)") (class "Default")
      (node (ref "U4") (pin "20") (pinfunction "20_20") (pintype "bidirectional"))
    )
    (net (code "86") (name "unconnected-(U4-Pad21)") (class "Default")
      (node (ref "U4") (pin "21") (pinfunction "21_21") (pintype "bidirectional"))
    )
    (net (code "87") (name "unconnected-(U4-Pad22)") (class "Default")
      (node (ref "U4") (pin "22") (pinfunction "22_22") (pintype "bidirectional"))
    )
    (net (code "88") (name "unconnected-(U4-Pad23)") (class "Default")
      (node (ref "U4") (pin "23") (pinfunction "23_23") (pintype "bidirectional"))
    )
    (net (code "89") (name "unconnected-(U4-Pad24)") (class "Default")
      (node (ref "U4") (pin "24") (pinfunction "24_24") (pintype "bidirectional"))
    )
    (net (code "90") (name "unconnected-(U4-Pad25)") (class "Default")
      (node (ref "U4") (pin "25") (pinfunction "25_25") (pintype "bidirectional"))
    )
    (net (code "91") (name "unconnected-(U4-Pad26)") (class "Default")
      (node (ref "U4") (pin "26") (pinfunction "26_26") (pintype "bidirectional"))
    )
    (net (code "92") (name "unconnected-(U4-Pad27)") (class "Default")
      (node (ref "U4") (pin "27") (pinfunction "27_27") (pintype "bidirectional"))
    )
    (net (code "93") (name "unconnected-(U4-Pad28)") (class "Default")
      (node (ref "U4") (pin "28") (pinfunction "28_28") (pintype "bidirectional"))
    )
    (net (code "94") (name "unconnected-(U4-Pad30)") (class "Default")
      (node (ref "U4") (pin "30") (pinfunction "30_30") (pintype "bidirectional"))
    )
    (net (code "95") (name "unconnected-(U4-Pad34)") (class "Default")
      (node (ref "U4") (pin "34") (pinfunction "34_34") (pintype "bidirectional"))
    )
    (net (code "96") (name "unconnected-(U4-Pad35)") (class "Default")
      (node (ref "U4") (pin "35") (pinfunction "35_35") (pintype "bidirectional"))
    )
    (net (code "97") (name "unconnected-(U4-Pad39)") (class "Default")
      (node (ref "U4") (pin "39") (pinfunction "39_39") (pintype "bidirectional"))
    )
    (net (code "98") (name "unconnected-(U4-Pad40)") (class "Default")
      (node (ref "U4") (pin "40") (pinfunction "40_40") (pintype "input"))
    )
    (net (code "99") (name "unconnected-(U4-Pad41)") (class "Default")
      (node (ref "U4") (pin "41") (pinfunction "41_41") (pintype "bidirectional"))
    )
    (net (code "100") (name "unconnected-(U4-Pad42)") (class "Default")
      (node (ref "U4") (pin "42") (pinfunction "42_42") (pintype "bidirectional"))
    )
    (net (code "101") (name "unconnected-(U4-Pad43)") (class "Default")
      (node (ref "U4") (pin "43") (pinfunction "43_43") (pintype "bidirectional"))
    )
    (net (code "102") (name "unconnected-(U4-Pad50)") (class "Default")
      (node (ref "U4") (pin "50") (pinfunction "50_50") (pintype "bidirectional"))
    )
    (net (code "103") (name "unconnected-(U4-Pad51)") (class "Default")
      (node (ref "U4") (pin "51") (pinfunction "51_51") (pintype "bidirectional"))
    )
    (net (code "104") (name "unconnected-(U4-Pad52)") (class "Default")
      (node (ref "U4") (pin "52") (pinfunction "52_52") (pintype "output"))
    )
    (net (code "105") (name "unconnected-(U4-Pad61)") (class "Default")
      (node (ref "U4") (pin "61") (pinfunction "61_61") (pintype "bidirectional"))
    )
    (net (code "106") (name "unconnected-(U11-Pad4)") (class "Default")
      (node (ref "U11") (pin "4") (pinfunction "4_4") (pintype "passive"))
    )
    (net (code "107") (name "unconnected-(X2-Pad2)") (class "Default")
      (node (ref "X2") (pin "2") (pinfunction "2_2") (pintype "bidirectional"))
    )
    (net (code "108") (name "unconnected-(X2-Pad6)") (class "Default")
      (node (ref "X2") (pin "6") (pinfunction "6_6") (pintype "bidirectional"))
    )
    (net (code "109") (name "unconnected-(X2-Pad8)") (class "Default")
      (node (ref "X2") (pin "8") (pinfunction "8_8") (pintype "bidirectional"))
    )
    (net (code "110") (name "unconnected-(X2-Pad10)") (class "Default")
      (node (ref "X2") (pin "10") (pinfunction "10_10") (pintype "bidirectional"))
    )
    (net (code "111") (name "unconnected-(X2-Pad12)") (class "Default")
      (node (ref "X2") (pin "12") (pinfunction "12_12") (pintype "bidirectional"))
    )
    (net (code "112") (name "unconnected-(X2-Pad13)") (class "Default")
      (node (ref "X2") (pin "13") (pinfunction "13_13") (pintype "bidirectional"))
    )
    (net (code "113") (name "unconnected-(X2-Pad14)") (class "Default")
      (node (ref "X2") (pin "14") (pinfunction "14_14") (pintype "bidirectional"))
    )
  )
)
